# design.net
KiCad netlist of a schematic drawn in Altium Designer
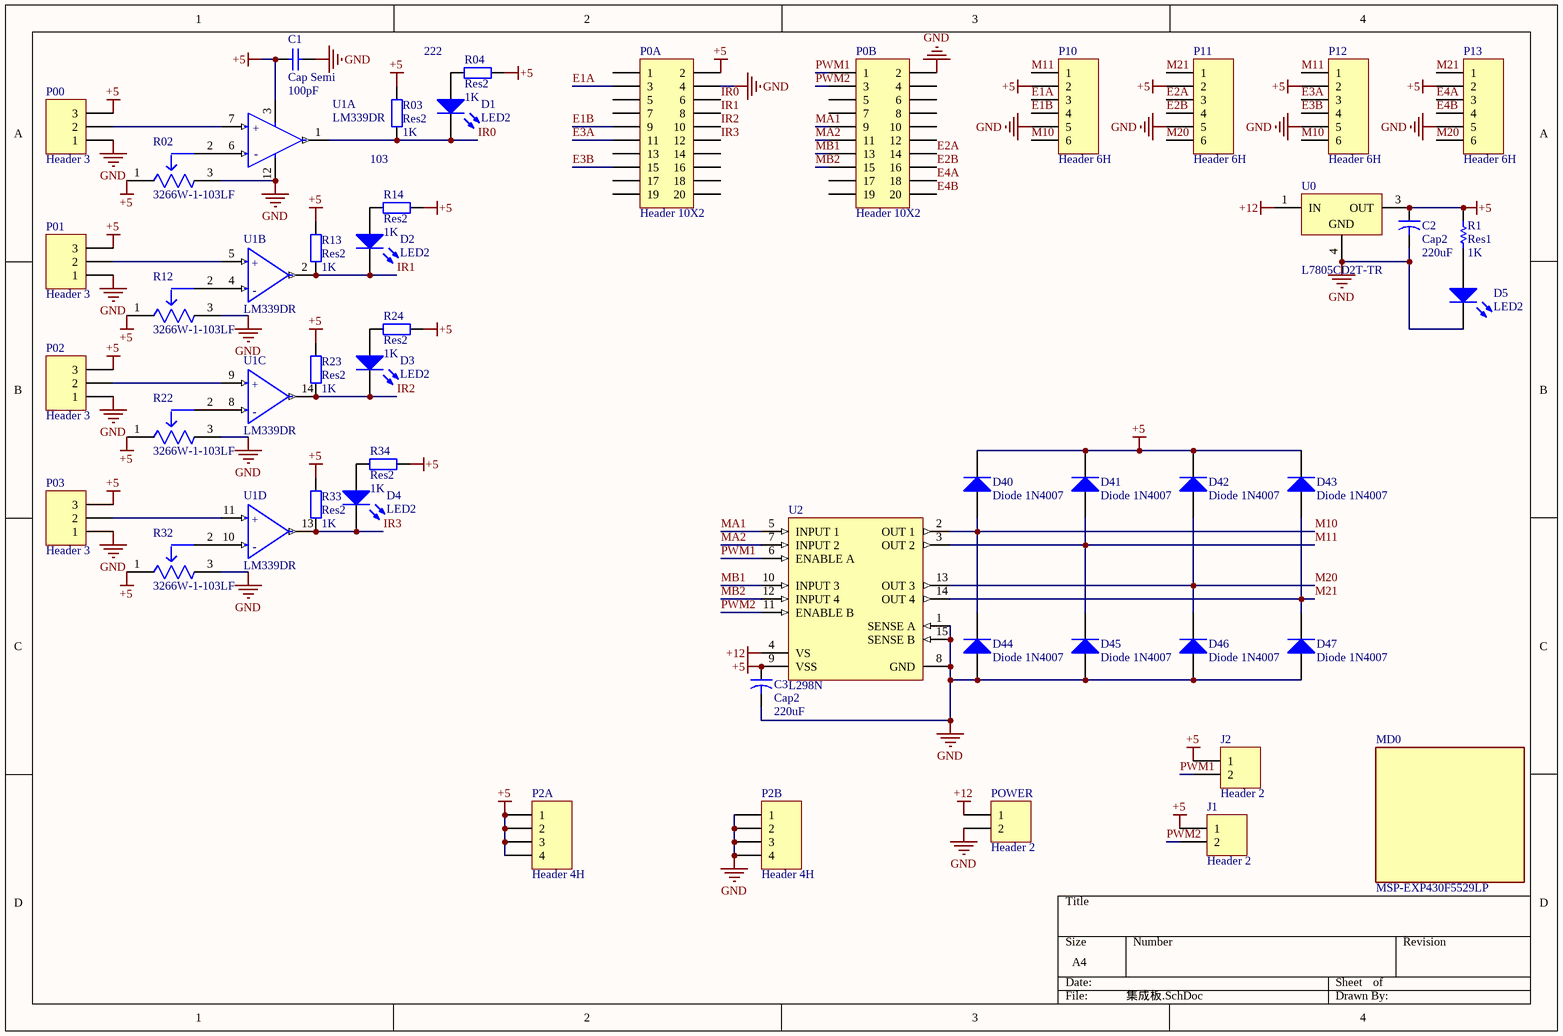
[diagram p0: 集成板.SchDoc]

(export (version "E")
  (design (tool "Eeschema 10.0.6"))
  (components
    (comp (ref "C1")
      (value "Cap Semi")
      (footprint "C1206")
      (description "Capacitor (Semiconductor SIM Model)")
      (fields (field (name "ALTIUM_VALUE") "100pF") (field (name "PUBLISHER") "Altium Limited"))
      (libsource (lib "Miscellaneous Devices") (part "Cap Semi"))
    )
    (comp (ref "C2")
      (value "Cap2")
      (footprint "CAPR5-4X5")
      (description "Capacitor")
      (fields (field (name "ALTIUM_VALUE") "220uF") (field (name "PUBLISHER") "Altium Limited"))
      (libsource (lib "Miscellaneous Devices") (part "Cap2"))
    )
    (comp (ref "C3")
      (value "Cap2")
      (footprint "CAPR5-4X5")
      (description "Capacitor")
      (fields (field (name "ALTIUM_VALUE") "220uF") (field (name "PUBLISHER") "Altium Limited"))
      (libsource (lib "Miscellaneous Devices") (part "Cap2"))
    )
    (comp (ref "D1")
      (value "LED2")
      (footprint "3.2X1.6X1.1")
      (description "Typical RED, GREEN, YELLOW, AMBER GaAs LED")
      (fields (field (name "PUBLISHER") "Altium Limited"))
      (libsource (lib "Miscellaneous Devices") (part "LED2"))
    )
    (comp (ref "D2")
      (value "LED2")
      (footprint "3.2X1.6X1.1")
      (description "Typical RED, GREEN, YELLOW, AMBER GaAs LED")
      (fields (field (name "PUBLISHER") "Altium Limited"))
      (libsource (lib "Miscellaneous Devices") (part "LED2"))
    )
    (comp (ref "D3")
      (value "LED2")
      (footprint "3.2X1.6X1.1")
      (description "Typical RED, GREEN, YELLOW, AMBER GaAs LED")
      (fields (field (name "PUBLISHER") "Altium Limited"))
      (libsource (lib "Miscellaneous Devices") (part "LED2"))
    )
    (comp (ref "D4")
      (value "LED2")
      (footprint "3.2X1.6X1.1")
      (description "Typical RED, GREEN, YELLOW, AMBER GaAs LED")
      (fields (field (name "PUBLISHER") "Altium Limited"))
      (libsource (lib "Miscellaneous Devices") (part "LED2"))
    )
    (comp (ref "D5")
      (value "LED2")
      (footprint "3.2X1.6X1.1")
      (description "Typical RED, GREEN, YELLOW, AMBER GaAs LED")
      (fields (field (name "PUBLISHER") "Altium Limited"))
      (libsource (lib "Miscellaneous Devices") (part "LED2"))
    )
    (comp (ref "D40")
      (value "Diode 1N4007")
      (footprint "DO-41")
      (description "1 Amp General Purpose Rectifier")
      (fields (field (name "PUBLISHER") "Altium Limited"))
      (libsource (lib "Miscellaneous Devices") (part "Diode 1N4007"))
    )
    (comp (ref "D41")
      (value "Diode 1N4007")
      (footprint "DO-41")
      (description "1 Amp General Purpose Rectifier")
      (fields (field (name "PUBLISHER") "Altium Limited"))
      (libsource (lib "Miscellaneous Devices") (part "Diode 1N4007"))
    )
    (comp (ref "D42")
      (value "Diode 1N4007")
      (footprint "DO-41")
      (description "1 Amp General Purpose Rectifier")
      (fields (field (name "PUBLISHER") "Altium Limited"))
      (libsource (lib "Miscellaneous Devices") (part "Diode 1N4007"))
    )
    (comp (ref "D43")
      (value "Diode 1N4007")
      (footprint "DO-41")
      (description "1 Amp General Purpose Rectifier")
      (fields (field (name "PUBLISHER") "Altium Limited"))
      (libsource (lib "Miscellaneous Devices") (part "Diode 1N4007"))
    )
    (comp (ref "D44")
      (value "Diode 1N4007")
      (footprint "DO-41")
      (description "1 Amp General Purpose Rectifier")
      (fields (field (name "PUBLISHER") "Altium Limited"))
      (libsource (lib "Miscellaneous Devices") (part "Diode 1N4007"))
    )
    (comp (ref "D45")
      (value "Diode 1N4007")
      (footprint "DO-41")
      (description "1 Amp General Purpose Rectifier")
      (fields (field (name "PUBLISHER") "Altium Limited"))
      (libsource (lib "Miscellaneous Devices") (part "Diode 1N4007"))
    )
    (comp (ref "D46")
      (value "Diode 1N4007")
      (footprint "DO-41")
      (description "1 Amp General Purpose Rectifier")
      (fields (field (name "PUBLISHER") "Altium Limited"))
      (libsource (lib "Miscellaneous Devices") (part "Diode 1N4007"))
    )
    (comp (ref "D47")
      (value "Diode 1N4007")
      (footprint "DO-41")
      (description "1 Amp General Purpose Rectifier")
      (fields (field (name "PUBLISHER") "Altium Limited"))
      (libsource (lib "Miscellaneous Devices") (part "Diode 1N4007"))
    )
    (comp (ref "J1")
      (value "Header 2")
      (footprint "HDR1X2")
      (description "Header, 2-Pin")
      (fields (field (name "PUBLISHER") "Altium Limited"))
      (libsource (lib "Miscellaneous Connectors") (part "Header 2"))
    )
    (comp (ref "J2")
      (value "Header 2")
      (footprint "HDR1X2")
      (description "Header, 2-Pin")
      (fields (field (name "PUBLISHER") "Altium Limited"))
      (libsource (lib "Miscellaneous Connectors") (part "Header 2"))
    )
    (comp (ref "MD0")
      (value "MSP-EXP430F5529LP")
      (footprint "FP-MSP-EXP430F5529LP-MFG")
      (description "LAUNCHPAD MSP430F5529 EVAL BRD")
      (fields
        (field (name "MANUFACTURER") "Texas Instruments")
        (field (name "OCTOPART") "https://octopart.com/msp-exp430f5529lp-texas+instruments-30356695")
      )
      (libsource (lib "Altium Content Vault") (part "acc72977dbe8eae022b9b1b147063ea"))
    )
    (comp (ref "P00")
      (value "Header 3")
      (footprint "HDR1X3")
      (description "Header, 3-Pin")
      (fields (field (name "PUBLISHER") "Altium Limited"))
      (libsource (lib "Miscellaneous Connectors") (part "Header 3"))
    )
    (comp (ref "P0A")
      (value "Header 10X2")
      (footprint "HDR2X10")
      (description "Header, 10-Pin, Dual row")
      (fields (field (name "PUBLISHER") "Altium Limited"))
      (libsource (lib "Miscellaneous Connectors") (part "Header 10X2"))
    )
    (comp (ref "P0B")
      (value "Header 10X2")
      (footprint "HDR2X10")
      (description "Header, 10-Pin, Dual row")
      (fields (field (name "PUBLISHER") "Altium Limited"))
      (libsource (lib "Miscellaneous Connectors") (part "Header 10X2"))
    )
    (comp (ref "P01")
      (value "Header 3")
      (footprint "HDR1X3")
      (description "Header, 3-Pin")
      (fields (field (name "PUBLISHER") "Altium Limited"))
      (libsource (lib "Miscellaneous Connectors") (part "Header 3"))
    )
    (comp (ref "P02")
      (value "Header 3")
      (footprint "HDR1X3")
      (description "Header, 3-Pin")
      (fields (field (name "PUBLISHER") "Altium Limited"))
      (libsource (lib "Miscellaneous Connectors") (part "Header 3"))
    )
    (comp (ref "P2A")
      (value "Header 4H")
      (footprint "HDR1X4H")
      (description "Header, 4-Pin, Right Angle")
      (fields (field (name "PUBLISHER") "Altium Limited"))
      (libsource (lib "Miscellaneous Connectors") (part "Header 4H"))
    )
    (comp (ref "P2B")
      (value "Header 4H")
      (footprint "HDR1X4H")
      (description "Header, 4-Pin, Right Angle")
      (fields (field (name "PUBLISHER") "Altium Limited"))
      (libsource (lib "Miscellaneous Connectors") (part "Header 4H"))
    )
    (comp (ref "P03")
      (value "Header 3")
      (footprint "HDR1X3")
      (description "Header, 3-Pin")
      (fields (field (name "PUBLISHER") "Altium Limited"))
      (libsource (lib "Miscellaneous Connectors") (part "Header 3"))
    )
    (comp (ref "P10")
      (value "Header 6H")
      (footprint "HDR1X6H")
      (description "Header, 6-Pin, Right Angle")
      (fields (field (name "PUBLISHER") "Altium Limited"))
      (libsource (lib "Miscellaneous Connectors") (part "Header 6H"))
    )
    (comp (ref "P11")
      (value "Header 6H")
      (footprint "HDR1X6H")
      (description "Header, 6-Pin, Right Angle")
      (fields (field (name "PUBLISHER") "Altium Limited"))
      (libsource (lib "Miscellaneous Connectors") (part "Header 6H"))
    )
    (comp (ref "P12")
      (value "Header 6H")
      (footprint "HDR1X6H")
      (description "Header, 6-Pin, Right Angle")
      (fields (field (name "PUBLISHER") "Altium Limited"))
      (libsource (lib "Miscellaneous Connectors") (part "Header 6H"))
    )
    (comp (ref "P13")
      (value "Header 6H")
      (footprint "HDR1X6H")
      (description "Header, 6-Pin, Right Angle")
      (fields (field (name "PUBLISHER") "Altium Limited"))
      (libsource (lib "Miscellaneous Connectors") (part "Header 6H"))
    )
    (comp (ref "POWER")
      (value "Header 2")
      (footprint "HDR1X2")
      (description "Header, 2-Pin")
      (fields (field (name "PUBLISHER") "Altium Limited"))
      (libsource (lib "Miscellaneous Connectors") (part "Header 2"))
    )
    (comp (ref "R1")
      (value "Res1")
      (footprint "AXIAL-0.3")
      (description "Resistor")
      (fields (field (name "ALTIUM_VALUE") "1K") (field (name "PUBLISHER") "Altium Limited"))
      (libsource (lib "Miscellaneous Devices") (part "Res1"))
    )
    (comp (ref "R02")
      (value "3266W-1-103LF")
      (footprint "FP-3266W-MFG")
      (description "TRIMMER 10K OHM 0.25W PC PIN TOP")
      (fields
        (field (name "MANUFACTURER") "Bourns")
        (field (name "OCTOPART") "https://octopart.com/3266w-1-103lf-bourns-81445")
      )
      (libsource (lib "Altium Content Vault") (part "5aa38b60e553f01fbee9df648f8b81b"))
    )
    (comp (ref "R03")
      (value "Res2")
      (footprint "C1206")
      (description "Resistor")
      (fields (field (name "ALTIUM_VALUE") "1K") (field (name "PUBLISHER") "Altium Limited"))
      (libsource (lib "") (part "Res2_1"))
    )
    (comp (ref "R04")
      (value "Res2")
      (footprint "C1206")
      (description "Resistor")
      (fields (field (name "ALTIUM_VALUE") "1K") (field (name "PUBLISHER") "Altium Limited"))
      (libsource (lib "") (part "Res2_3"))
    )
    (comp (ref "R12")
      (value "3266W-1-103LF")
      (footprint "FP-3266W-MFG")
      (description "TRIMMER 10K OHM 0.25W PC PIN TOP")
      (fields
        (field (name "MANUFACTURER") "Bourns")
        (field (name "OCTOPART") "https://octopart.com/3266w-1-103lf-bourns-81445")
      )
      (libsource (lib "Altium Content Vault") (part "5aa38b60e553f01fbee9df648f8b81b"))
    )
    (comp (ref "R13")
      (value "Res2")
      (footprint "C1206")
      (description "Resistor")
      (fields (field (name "ALTIUM_VALUE") "1K") (field (name "PUBLISHER") "Altium Limited"))
      (libsource (lib "") (part "Res2_1"))
    )
    (comp (ref "R14")
      (value "Res2")
      (footprint "C1206")
      (description "Resistor")
      (fields (field (name "ALTIUM_VALUE") "1K") (field (name "PUBLISHER") "Altium Limited"))
      (libsource (lib "Miscellaneous Devices") (part "Res2"))
    )
    (comp (ref "R22")
      (value "3266W-1-103LF")
      (footprint "FP-3266W-MFG")
      (description "TRIMMER 10K OHM 0.25W PC PIN TOP")
      (fields
        (field (name "MANUFACTURER") "Bourns")
        (field (name "OCTOPART") "https://octopart.com/3266w-1-103lf-bourns-81445")
      )
      (libsource (lib "Altium Content Vault") (part "5aa38b60e553f01fbee9df648f8b81b"))
    )
    (comp (ref "R23")
      (value "Res2")
      (footprint "C1206")
      (description "Resistor")
      (fields (field (name "ALTIUM_VALUE") "1K") (field (name "PUBLISHER") "Altium Limited"))
      (libsource (lib "") (part "Res2_2"))
    )
    (comp (ref "R24")
      (value "Res2")
      (footprint "C1206")
      (description "Resistor")
      (fields (field (name "ALTIUM_VALUE") "1K") (field (name "PUBLISHER") "Altium Limited"))
      (libsource (lib "Miscellaneous Devices") (part "Res2"))
    )
    (comp (ref "R32")
      (value "3266W-1-103LF")
      (footprint "FP-3266W-MFG")
      (description "TRIMMER 10K OHM 0.25W PC PIN TOP")
      (fields
        (field (name "MANUFACTURER") "Bourns")
        (field (name "OCTOPART") "https://octopart.com/3266w-1-103lf-bourns-81445")
      )
      (libsource (lib "Altium Content Vault") (part "5aa38b60e553f01fbee9df648f8b81b"))
    )
    (comp (ref "R33")
      (value "Res2")
      (footprint "C1206")
      (description "Resistor")
      (fields (field (name "ALTIUM_VALUE") "1K") (field (name "PUBLISHER") "Altium Limited"))
      (libsource (lib "") (part "Res2_1"))
    )
    (comp (ref "R34")
      (value "Res2")
      (footprint "C1206")
      (description "Resistor")
      (fields (field (name "ALTIUM_VALUE") "1K") (field (name "PUBLISHER") "Altium Limited"))
      (libsource (lib "Miscellaneous Devices") (part "Res2"))
    )
    (comp (ref "U0")
      (value "L7805CD2T-TR")
      (footprint "TO-263_M")
      (description "Positive Voltage Regulator, 3-Pin D2PAK, Tape and Reel")
      (libsource (lib "Altium Content Vault") (part "PM-REG-L4940-SOT3"))
    )
    (comp (ref "U1")
      (value "LM339DR")
      (footprint "FP-D0014A-MFG")
      (description "IC QUAD DIFF COMP 14-SOIC")
      (fields
        (field (name "OCTOPART") "https://octopart.com/lm339dr-texas+instruments-45532")
        (field (name "MANUFACTURER") "Texas Instruments")
      )
      (libsource (lib "Altium Content Vault") (part "e40d3f79f05c88e03941af0c3538ad1"))
    )
    (comp (ref "U2")
      (value "L298N")
      (footprint "STM-FM-15")
      (description "Dual Full-Bridge Driver, 4.8 to 46 V, -40 to 150 degC, 15-Pin FM (MW 15L), RoHS, Tube")
      (fields (field (name "MANUFACTURER") "STMicroelectronics") (field (name "PARTNUMBER") "L298"))
      (libsource (lib "Altium Content Vault") (part "STM-L298-15"))
    )
  )
  (nets
    (net (code "1") (name "+5") (class "Default")
      (node (ref "C1") (pin "1") (pinfunction "1_1") (pintype "passive"))
      (node (ref "C2") (pin "1") (pinfunction "1_1") (pintype "passive"))
      (node (ref "C3") (pin "1") (pinfunction "1_1") (pintype "passive"))
      (node (ref "D40") (pin "2") (pinfunction "K_2") (pintype "passive"))
      (node (ref "D41") (pin "2") (pinfunction "K_2") (pintype "passive"))
      (node (ref "D42") (pin "2") (pinfunction "K_2") (pintype "passive"))
      (node (ref "D43") (pin "2") (pinfunction "K_2") (pintype "passive"))
      (node (ref "J1") (pin "1") (pinfunction "1_1") (pintype "passive"))
      (node (ref "J2") (pin "1") (pinfunction "1_1") (pintype "passive"))
      (node (ref "P00") (pin "3") (pinfunction "3_3") (pintype "passive"))
      (node (ref "P01") (pin "3") (pinfunction "3_3") (pintype "passive"))
      (node (ref "P02") (pin "3") (pinfunction "3_3") (pintype "passive"))
      (node (ref "P03") (pin "3") (pinfunction "3_3") (pintype "passive"))
      (node (ref "P0A") (pin "2") (pinfunction "2_2") (pintype "passive"))
      (node (ref "P10") (pin "2") (pinfunction "2_2") (pintype "passive"))
      (node (ref "P11") (pin "2") (pinfunction "2_2") (pintype "passive"))
      (node (ref "P12") (pin "2") (pinfunction "2_2") (pintype "passive"))
      (node (ref "P13") (pin "2") (pinfunction "2_2") (pintype "passive"))
      (node (ref "P2A") (pin "1") (pinfunction "1_1") (pintype "passive"))
      (node (ref "P2A") (pin "2") (pinfunction "2_2") (pintype "passive"))
      (node (ref "P2A") (pin "3") (pinfunction "3_3") (pintype "passive"))
      (node (ref "P2A") (pin "4") (pinfunction "4_4") (pintype "passive"))
      (node (ref "R02") (pin "1") (pinfunction "CCW_1") (pintype "passive"))
      (node (ref "R03") (pin "2") (pinfunction "2_2") (pintype "passive"))
      (node (ref "R04") (pin "1") (pinfunction "1_1") (pintype "passive"))
      (node (ref "R1") (pin "2") (pinfunction "2_2") (pintype "passive"))
      (node (ref "R12") (pin "1") (pinfunction "CCW_1") (pintype "passive"))
      (node (ref "R13") (pin "2") (pinfunction "2_2") (pintype "passive"))
      (node (ref "R14") (pin "2") (pinfunction "2_2") (pintype "passive"))
      (node (ref "R22") (pin "1") (pinfunction "CCW_1") (pintype "passive"))
      (node (ref "R23") (pin "1") (pinfunction "1_1") (pintype "passive"))
      (node (ref "R24") (pin "2") (pinfunction "2_2") (pintype "passive"))
      (node (ref "R32") (pin "1") (pinfunction "CCW_1") (pintype "passive"))
      (node (ref "R33") (pin "2") (pinfunction "2_2") (pintype "passive"))
      (node (ref "R34") (pin "2") (pinfunction "2_2") (pintype "passive"))
      (node (ref "U0") (pin "3") (pinfunction "OUT_3") (pintype "power_in"))
      (node (ref "U1") (pin "3") (pinfunction "VCC_3") (pintype "power_in"))
      (node (ref "U2") (pin "9") (pinfunction "VSS_9") (pintype "power_in"))
    )
    (net (code "2") (name "+12") (class "Default")
      (node (ref "POWER") (pin "1") (pinfunction "1_1") (pintype "passive"))
      (node (ref "U0") (pin "1") (pinfunction "IN_1") (pintype "power_in"))
      (node (ref "U2") (pin "4") (pinfunction "VS_4") (pintype "power_in"))
    )
    (net (code "4") (name "/E1A") (class "Default")
      (node (ref "P0A") (pin "3") (pinfunction "3_3") (pintype "passive"))
      (node (ref "P10") (pin "3") (pinfunction "3_3") (pintype "passive"))
    )
    (net (code "5") (name "/E1B") (class "Default")
      (node (ref "P0A") (pin "9") (pinfunction "9_9") (pintype "passive"))
      (node (ref "P10") (pin "4") (pinfunction "4_4") (pintype "passive"))
    )
    (net (code "6") (name "/E2A") (class "Default")
      (node (ref "P0B") (pin "14") (pinfunction "14_14") (pintype "passive"))
      (node (ref "P11") (pin "3") (pinfunction "3_3") (pintype "passive"))
    )
    (net (code "7") (name "/E2B") (class "Default")
      (node (ref "P0B") (pin "16") (pinfunction "16_16") (pintype "passive"))
      (node (ref "P11") (pin "4") (pinfunction "4_4") (pintype "passive"))
    )
    (net (code "8") (name "/E3A") (class "Default")
      (node (ref "P0A") (pin "11") (pinfunction "11_11") (pintype "passive"))
      (node (ref "P12") (pin "3") (pinfunction "3_3") (pintype "passive"))
    )
    (net (code "9") (name "/E3B") (class "Default")
      (node (ref "P0A") (pin "15") (pinfunction "15_15") (pintype "passive"))
      (node (ref "P12") (pin "4") (pinfunction "4_4") (pintype "passive"))
    )
    (net (code "10") (name "/E4A") (class "Default")
      (node (ref "P0B") (pin "18") (pinfunction "18_18") (pintype "passive"))
      (node (ref "P13") (pin "3") (pinfunction "3_3") (pintype "passive"))
    )
    (net (code "11") (name "/E4B") (class "Default")
      (node (ref "P0B") (pin "20") (pinfunction "20_20") (pintype "passive"))
      (node (ref "P13") (pin "4") (pinfunction "4_4") (pintype "passive"))
    )
    (net (code "12") (name "/IR0") (class "Default")
      (node (ref "D1") (pin "2") (pinfunction "K_2") (pintype "passive"))
      (node (ref "P0A") (pin "6") (pinfunction "6_6") (pintype "passive"))
      (node (ref "R03") (pin "1") (pinfunction "1_1") (pintype "passive"))
      (node (ref "U1") (pin "1") (pinfunction "1OUT_1") (pintype "output"))
    )
    (net (code "13") (name "/IR1") (class "Default")
      (node (ref "D2") (pin "2") (pinfunction "K_2") (pintype "passive"))
      (node (ref "P0A") (pin "8") (pinfunction "8_8") (pintype "passive"))
      (node (ref "R13") (pin "1") (pinfunction "1_1") (pintype "passive"))
      (node (ref "U1") (pin "2") (pinfunction "2OUT_2") (pintype "output"))
    )
    (net (code "14") (name "/IR2") (class "Default")
      (node (ref "D3") (pin "2") (pinfunction "K_2") (pintype "passive"))
      (node (ref "P0A") (pin "10") (pinfunction "10_10") (pintype "passive"))
      (node (ref "R23") (pin "2") (pinfunction "2_2") (pintype "passive"))
      (node (ref "U1") (pin "14") (pinfunction "OUT3_14") (pintype "output"))
    )
    (net (code "15") (name "/IR3") (class "Default")
      (node (ref "D4") (pin "2") (pinfunction "K_2") (pintype "passive"))
      (node (ref "P0A") (pin "12") (pinfunction "12_12") (pintype "passive"))
      (node (ref "R33") (pin "1") (pinfunction "1_1") (pintype "passive"))
      (node (ref "U1") (pin "13") (pinfunction "OUT4_13") (pintype "output"))
    )
    (net (code "16") (name "/M10") (class "Default")
      (node (ref "D40") (pin "1") (pinfunction "A_1") (pintype "passive"))
      (node (ref "D44") (pin "2") (pinfunction "K_2") (pintype "passive"))
      (node (ref "P10") (pin "6") (pinfunction "6_6") (pintype "passive"))
      (node (ref "P12") (pin "6") (pinfunction "6_6") (pintype "passive"))
      (node (ref "U2") (pin "2") (pinfunction "OUT_1_2") (pintype "output"))
    )
    (net (code "17") (name "/M11") (class "Default")
      (node (ref "D41") (pin "1") (pinfunction "A_1") (pintype "passive"))
      (node (ref "D45") (pin "2") (pinfunction "K_2") (pintype "passive"))
      (node (ref "P10") (pin "1") (pinfunction "1_1") (pintype "passive"))
      (node (ref "P12") (pin "1") (pinfunction "1_1") (pintype "passive"))
      (node (ref "U2") (pin "3") (pinfunction "OUT_2_3") (pintype "output"))
    )
    (net (code "18") (name "/M20") (class "Default")
      (node (ref "D42") (pin "1") (pinfunction "A_1") (pintype "passive"))
      (node (ref "D46") (pin "2") (pinfunction "K_2") (pintype "passive"))
      (node (ref "P11") (pin "6") (pinfunction "6_6") (pintype "passive"))
      (node (ref "P13") (pin "6") (pinfunction "6_6") (pintype "passive"))
      (node (ref "U2") (pin "13") (pinfunction "OUT_3_13") (pintype "output"))
    )
    (net (code "19") (name "/M21") (class "Default")
      (node (ref "D43") (pin "1") (pinfunction "A_1") (pintype "passive"))
      (node (ref "D47") (pin "2") (pinfunction "K_2") (pintype "passive"))
      (node (ref "P11") (pin "1") (pinfunction "1_1") (pintype "passive"))
      (node (ref "P13") (pin "1") (pinfunction "1_1") (pintype "passive"))
      (node (ref "U2") (pin "14") (pinfunction "OUT_4_14") (pintype "output"))
    )
    (net (code "20") (name "/MA1") (class "Default")
      (node (ref "P0B") (pin "9") (pinfunction "9_9") (pintype "passive"))
      (node (ref "U2") (pin "5") (pinfunction "INPUT_1_5") (pintype "input"))
    )
    (net (code "21") (name "/MA2") (class "Default")
      (node (ref "P0B") (pin "11") (pinfunction "11_11") (pintype "passive"))
      (node (ref "U2") (pin "7") (pinfunction "INPUT_2_7") (pintype "input"))
    )
    (net (code "22") (name "/MB1") (class "Default")
      (node (ref "P0B") (pin "13") (pinfunction "13_13") (pintype "passive"))
      (node (ref "U2") (pin "10") (pinfunction "INPUT_3_10") (pintype "input"))
    )
    (net (code "23") (name "/MB2") (class "Default")
      (node (ref "P0B") (pin "15") (pinfunction "15_15") (pintype "passive"))
      (node (ref "U2") (pin "12") (pinfunction "INPUT_4_12") (pintype "input"))
    )
    (net (code "24") (name "/PWM1") (class "Default")
      (node (ref "J2") (pin "2") (pinfunction "2_2") (pintype "passive"))
      (node (ref "P0B") (pin "1") (pinfunction "1_1") (pintype "passive"))
      (node (ref "U2") (pin "6") (pinfunction "ENABLE_A_6") (pintype "input"))
    )
    (net (code "25") (name "/PWM2") (class "Default")
      (node (ref "J1") (pin "2") (pinfunction "2_2") (pintype "passive"))
      (node (ref "P0B") (pin "3") (pinfunction "3_3") (pintype "passive"))
      (node (ref "U2") (pin "11") (pinfunction "ENABLE_B_11") (pintype "input"))
    )
    (net (code "26") (name "GND") (class "Default")
      (node (ref "C1") (pin "2") (pinfunction "2_2") (pintype "passive"))
      (node (ref "C2") (pin "2") (pinfunction "2_2") (pintype "passive"))
      (node (ref "C3") (pin "2") (pinfunction "2_2") (pintype "passive"))
      (node (ref "D44") (pin "1") (pinfunction "A_1") (pintype "passive"))
      (node (ref "D45") (pin "1") (pinfunction "A_1") (pintype "passive"))
      (node (ref "D46") (pin "1") (pinfunction "A_1") (pintype "passive"))
      (node (ref "D47") (pin "1") (pinfunction "A_1") (pintype "passive"))
      (node (ref "D5") (pin "2") (pinfunction "K_2") (pintype "passive"))
      (node (ref "P00") (pin "1") (pinfunction "1_1") (pintype "passive"))
      (node (ref "P01") (pin "1") (pinfunction "1_1") (pintype "passive"))
      (node (ref "P02") (pin "1") (pinfunction "1_1") (pintype "passive"))
      (node (ref "P03") (pin "1") (pinfunction "1_1") (pintype "passive"))
      (node (ref "P0A") (pin "4") (pinfunction "4_4") (pintype "passive"))
      (node (ref "P0B") (pin "2") (pinfunction "2_2") (pintype "passive"))
      (node (ref "P10") (pin "5") (pinfunction "5_5") (pintype "passive"))
      (node (ref "P11") (pin "5") (pinfunction "5_5") (pintype "passive"))
      (node (ref "P12") (pin "5") (pinfunction "5_5") (pintype "passive"))
      (node (ref "P13") (pin "5") (pinfunction "5_5") (pintype "passive"))
      (node (ref "P2B") (pin "1") (pinfunction "1_1") (pintype "passive"))
      (node (ref "P2B") (pin "2") (pinfunction "2_2") (pintype "passive"))
      (node (ref "P2B") (pin "3") (pinfunction "3_3") (pintype "passive"))
      (node (ref "P2B") (pin "4") (pinfunction "4_4") (pintype "passive"))
      (node (ref "POWER") (pin "2") (pinfunction "2_2") (pintype "passive"))
      (node (ref "R02") (pin "3") (pinfunction "CW_3") (pintype "passive"))
      (node (ref "R12") (pin "3") (pinfunction "CW_3") (pintype "passive"))
      (node (ref "R22") (pin "3") (pinfunction "CW_3") (pintype "passive"))
      (node (ref "R32") (pin "3") (pinfunction "CW_3") (pintype "passive"))
      (node (ref "U0") (pin "4") (pinfunction "GND_4") (pintype "power_in"))
      (node (ref "U1") (pin "12") (pinfunction "GND_12") (pintype "power_in"))
      (node (ref "U2") (pin "1") (pinfunction "SENSE_A_1") (pintype "input"))
      (node (ref "U2") (pin "15") (pinfunction "SENSE_B_15") (pintype "input"))
      (node (ref "U2") (pin "8") (pinfunction "GND_8") (pintype "power_in"))
    )
    (net (code "27") (name "Net-(D1-A)") (class "Default")
      (node (ref "D1") (pin "1") (pinfunction "A_1") (pintype "passive"))
      (node (ref "R04") (pin "2") (pinfunction "2_2") (pintype "passive"))
    )
    (net (code "28") (name "Net-(D2-A)") (class "Default")
      (node (ref "D2") (pin "1") (pinfunction "A_1") (pintype "passive"))
      (node (ref "R14") (pin "1") (pinfunction "1_1") (pintype "passive"))
    )
    (net (code "29") (name "Net-(D3-A)") (class "Default")
      (node (ref "D3") (pin "1") (pinfunction "A_1") (pintype "passive"))
      (node (ref "R24") (pin "1") (pinfunction "1_1") (pintype "passive"))
    )
    (net (code "30") (name "Net-(D4-A)") (class "Default")
      (node (ref "D4") (pin "1") (pinfunction "A_1") (pintype "passive"))
      (node (ref "R34") (pin "1") (pinfunction "1_1") (pintype "passive"))
    )
    (net (code "31") (name "Net-(D5-A)") (class "Default")
      (node (ref "D5") (pin "1") (pinfunction "A_1") (pintype "passive"))
      (node (ref "R1") (pin "1") (pinfunction "1_1") (pintype "passive"))
    )
    (net (code "32") (name "Net-(R02-WIPER)") (class "Default")
      (node (ref "R02") (pin "2") (pinfunction "WIPER_2") (pintype "passive"))
      (node (ref "U1") (pin "6") (pinfunction "1IN-_6") (pintype "input"))
    )
    (net (code "33") (name "Net-(R12-WIPER)") (class "Default")
      (node (ref "R12") (pin "2") (pinfunction "WIPER_2") (pintype "passive"))
      (node (ref "U1") (pin "4") (pinfunction "2IN-_4") (pintype "input"))
    )
    (net (code "34") (name "Net-(R22-WIPER)") (class "Default")
      (node (ref "R22") (pin "2") (pinfunction "WIPER_2") (pintype "passive"))
      (node (ref "U1") (pin "8") (pinfunction "3IN-_8") (pintype "input"))
    )
    (net (code "35") (name "Net-(R32-WIPER)") (class "Default")
      (node (ref "R32") (pin "2") (pinfunction "WIPER_2") (pintype "passive"))
      (node (ref "U1") (pin "10") (pinfunction "4IN-_10") (pintype "input"))
    )
    (net (code "36") (name "Net-(U1A-1IN+)") (class "Default")
      (node (ref "P00") (pin "2") (pinfunction "2_2") (pintype "passive"))
      (node (ref "U1") (pin "7") (pinfunction "1IN+_7") (pintype "input"))
    )
    (net (code "37") (name "Net-(U1B-2IN+)") (class "Default")
      (node (ref "P01") (pin "2") (pinfunction "2_2") (pintype "passive"))
      (node (ref "U1") (pin "5") (pinfunction "2IN+_5") (pintype "input"))
    )
    (net (code "38") (name "Net-(U1C-3IN+)") (class "Default")
      (node (ref "P02") (pin "2") (pinfunction "2_2") (pintype "passive"))
      (node (ref "U1") (pin "9") (pinfunction "3IN+_9") (pintype "input"))
    )
    (net (code "39") (name "Net-(U1D-4IN+)") (class "Default")
      (node (ref "P03") (pin "2") (pinfunction "2_2") (pintype "passive"))
      (node (ref "U1") (pin "11") (pinfunction "4IN+_11") (pintype "input"))
    )
    (net (code "40") (name "unconnected-(P0A-Pad1)") (class "Default")
      (node (ref "P0A") (pin "1") (pinfunction "1_1") (pintype "passive"))
    )
    (net (code "41") (name "unconnected-(P0A-Pad5)") (class "Default")
      (node (ref "P0A") (pin "5") (pinfunction "5_5") (pintype "passive"))
    )
    (net (code "42") (name "unconnected-(P0A-Pad7)") (class "Default")
      (node (ref "P0A") (pin "7") (pinfunction "7_7") (pintype "passive"))
    )
    (net (code "43") (name "unconnected-(P0A-Pad13)") (class "Default")
      (node (ref "P0A") (pin "13") (pinfunction "13_13") (pintype "passive"))
    )
    (net (code "44") (name "unconnected-(P0A-Pad14)") (class "Default")
      (node (ref "P0A") (pin "14") (pinfunction "14_14") (pintype "passive"))
    )
    (net (code "45") (name "unconnected-(P0A-Pad16)") (class "Default")
      (node (ref "P0A") (pin "16") (pinfunction "16_16") (pintype "passive"))
    )
    (net (code "46") (name "unconnected-(P0A-Pad17)") (class "Default")
      (node (ref "P0A") (pin "17") (pinfunction "17_17") (pintype "passive"))
    )
    (net (code "47") (name "unconnected-(P0A-Pad18)") (class "Default")
      (node (ref "P0A") (pin "18") (pinfunction "18_18") (pintype "passive"))
    )
    (net (code "48") (name "unconnected-(P0A-Pad19)") (class "Default")
      (node (ref "P0A") (pin "19") (pinfunction "19_19") (pintype "passive"))
    )
    (net (code "49") (name "unconnected-(P0A-Pad20)") (class "Default")
      (node (ref "P0A") (pin "20") (pinfunction "20_20") (pintype "passive"))
    )
    (net (code "50") (name "unconnected-(P0B-Pad4)") (class "Default")
      (node (ref "P0B") (pin "4") (pinfunction "4_4") (pintype "passive"))
    )
    (net (code "51") (name "unconnected-(P0B-Pad5)") (class "Default")
      (node (ref "P0B") (pin "5") (pinfunction "5_5") (pintype "passive"))
    )
    (net (code "52") (name "unconnected-(P0B-Pad6)") (class "Default")
      (node (ref "P0B") (pin "6") (pinfunction "6_6") (pintype "passive"))
    )
    (net (code "53") (name "unconnected-(P0B-Pad7)") (class "Default")
      (node (ref "P0B") (pin "7") (pinfunction "7_7") (pintype "passive"))
    )
    (net (code "54") (name "unconnected-(P0B-Pad8)") (class "Default")
      (node (ref "P0B") (pin "8") (pinfunction "8_8") (pintype "passive"))
    )
    (net (code "55") (name "unconnected-(P0B-Pad10)") (class "Default")
      (node (ref "P0B") (pin "10") (pinfunction "10_10") (pintype "passive"))
    )
    (net (code "56") (name "unconnected-(P0B-Pad12)") (class "Default")
      (node (ref "P0B") (pin "12") (pinfunction "12_12") (pintype "passive"))
    )
    (net (code "57") (name "unconnected-(P0B-Pad17)") (class "Default")
      (node (ref "P0B") (pin "17") (pinfunction "17_17") (pintype "passive"))
    )
    (net (code "58") (name "unconnected-(P0B-Pad19)") (class "Default")
      (node (ref "P0B") (pin "19") (pinfunction "19_19") (pintype "passive"))
    )
  )
)
